# WindVane.net
KiCad netlist of a schematic drawn in EAGLE
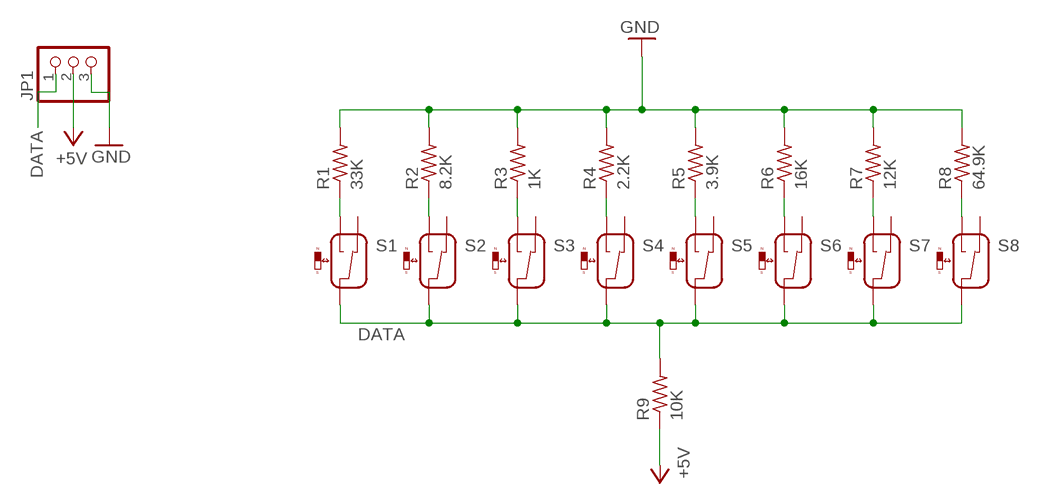
[diagram p0: schematic, sheet 1]

(export (version "E")
  (design (tool "Eeschema 10.0.6"))
  (components
    (comp (ref "JP1")
      (value "PINHD-1X3/90")
      (footprint "eagle-import:1X03_90")
      (libsource (lib "eagle-import") (part "PINHD-1X3/90"))
    )
    (comp (ref "R1")
      (value "33K")
      (footprint "eagle-import:0207_10")
      (libsource (lib "eagle-import") (part "R-US_0207/10"))
    )
    (comp (ref "R2")
      (value "8.2K")
      (footprint "eagle-import:0207_10")
      (libsource (lib "eagle-import") (part "R-US_0207/10"))
    )
    (comp (ref "R3")
      (value "1K")
      (footprint "eagle-import:0207_10")
      (libsource (lib "eagle-import") (part "R-US_0207/10"))
    )
    (comp (ref "R4")
      (value "2.2K")
      (footprint "eagle-import:0207_10")
      (libsource (lib "eagle-import") (part "R-US_0207/10"))
    )
    (comp (ref "R5")
      (value "3.9K")
      (footprint "eagle-import:0207_10")
      (libsource (lib "eagle-import") (part "R-US_0207/10"))
    )
    (comp (ref "R6")
      (value "16K")
      (footprint "eagle-import:0207_10")
      (libsource (lib "eagle-import") (part "R-US_0207/10"))
    )
    (comp (ref "R7")
      (value "12K")
      (footprint "eagle-import:0207_10")
      (libsource (lib "eagle-import") (part "R-US_0207/10"))
    )
    (comp (ref "R8")
      (value "64.9K")
      (footprint "eagle-import:0207_10")
      (libsource (lib "eagle-import") (part "R-US_0207/10"))
    )
    (comp (ref "R9")
      (value "10K")
      (footprint "eagle-import:0207_10")
      (libsource (lib "eagle-import") (part "R-US_0207/10"))
    )
    (comp (ref "S1")
      (value "REED-SWITCH-NO-NC")
      (footprint "eagle-import:MK6-8-C")
      (libsource (lib "eagle-import") (part "REED-SWITCH-NO-NC"))
    )
    (comp (ref "S2")
      (value "REED-SWITCH-NO-NC")
      (footprint "eagle-import:MK6-8-C")
      (libsource (lib "eagle-import") (part "REED-SWITCH-NO-NC"))
    )
    (comp (ref "S3")
      (value "REED-SWITCH-NO-NC")
      (footprint "eagle-import:MK6-8-C")
      (libsource (lib "eagle-import") (part "REED-SWITCH-NO-NC"))
    )
    (comp (ref "S4")
      (value "REED-SWITCH-NO-NC")
      (footprint "eagle-import:MK6-8-C")
      (libsource (lib "eagle-import") (part "REED-SWITCH-NO-NC"))
    )
    (comp (ref "S5")
      (value "REED-SWITCH-NO-NC")
      (footprint "eagle-import:MK6-8-C")
      (libsource (lib "eagle-import") (part "REED-SWITCH-NO-NC"))
    )
    (comp (ref "S6")
      (value "REED-SWITCH-NO-NC")
      (footprint "eagle-import:MK6-8-C")
      (libsource (lib "eagle-import") (part "REED-SWITCH-NO-NC"))
    )
    (comp (ref "S7")
      (value "REED-SWITCH-NO-NC")
      (footprint "eagle-import:MK6-8-C")
      (libsource (lib "eagle-import") (part "REED-SWITCH-NO-NC"))
    )
    (comp (ref "S8")
      (value "REED-SWITCH-NO-NC")
      (footprint "eagle-import:MK6-8-C")
      (libsource (lib "eagle-import") (part "REED-SWITCH-NO-NC"))
    )
  )
  (nets
    (net (code "1") (name "+5V") (class "Default")
      (node (ref "JP1") (pin "2") (pinfunction "2_2") (pintype "passive"))
      (node (ref "R9") (pin "1") (pinfunction "1_1") (pintype "passive"))
    )
    (net (code "2") (name "/DATA") (class "Default")
      (node (ref "JP1") (pin "1") (pinfunction "1_1") (pintype "passive"))
      (node (ref "R9") (pin "2") (pinfunction "2_2") (pintype "passive"))
      (node (ref "S1") (pin "COM") (pinfunction "COM_COM") (pintype "passive"))
      (node (ref "S2") (pin "COM") (pinfunction "COM_COM") (pintype "passive"))
      (node (ref "S3") (pin "COM") (pinfunction "COM_COM") (pintype "passive"))
      (node (ref "S4") (pin "COM") (pinfunction "COM_COM") (pintype "passive"))
      (node (ref "S5") (pin "COM") (pinfunction "COM_COM") (pintype "passive"))
      (node (ref "S6") (pin "COM") (pinfunction "COM_COM") (pintype "passive"))
      (node (ref "S7") (pin "COM") (pinfunction "COM_COM") (pintype "passive"))
      (node (ref "S8") (pin "COM") (pinfunction "COM_COM") (pintype "passive"))
    )
    (net (code "3") (name "GND") (class "Default")
      (node (ref "JP1") (pin "3") (pinfunction "3_3") (pintype "passive"))
      (node (ref "R1") (pin "2") (pinfunction "2_2") (pintype "passive"))
      (node (ref "R2") (pin "2") (pinfunction "2_2") (pintype "passive"))
      (node (ref "R3") (pin "2") (pinfunction "2_2") (pintype "passive"))
      (node (ref "R4") (pin "2") (pinfunction "2_2") (pintype "passive"))
      (node (ref "R5") (pin "2") (pinfunction "2_2") (pintype "passive"))
      (node (ref "R6") (pin "2") (pinfunction "2_2") (pintype "passive"))
      (node (ref "R7") (pin "2") (pinfunction "2_2") (pintype "passive"))
      (node (ref "R8") (pin "2") (pinfunction "2_2") (pintype "passive"))
    )
    (net (code "4") (name "Net-(R1-Pad1)") (class "Default")
      (node (ref "R1") (pin "1") (pinfunction "1_1") (pintype "passive"))
      (node (ref "S1") (pin "NO") (pinfunction "NO_NO") (pintype "passive"))
    )
    (net (code "5") (name "Net-(R2-Pad1)") (class "Default")
      (node (ref "R2") (pin "1") (pinfunction "1_1") (pintype "passive"))
      (node (ref "S2") (pin "NO") (pinfunction "NO_NO") (pintype "passive"))
    )
    (net (code "6") (name "Net-(R3-Pad1)") (class "Default")
      (node (ref "R3") (pin "1") (pinfunction "1_1") (pintype "passive"))
      (node (ref "S3") (pin "NO") (pinfunction "NO_NO") (pintype "passive"))
    )
    (net (code "7") (name "Net-(R4-Pad1)") (class "Default")
      (node (ref "R4") (pin "1") (pinfunction "1_1") (pintype "passive"))
      (node (ref "S4") (pin "NO") (pinfunction "NO_NO") (pintype "passive"))
    )
    (net (code "8") (name "Net-(R5-Pad1)") (class "Default")
      (node (ref "R5") (pin "1") (pinfunction "1_1") (pintype "passive"))
      (node (ref "S5") (pin "NO") (pinfunction "NO_NO") (pintype "passive"))
    )
    (net (code "9") (name "Net-(R6-Pad1)") (class "Default")
      (node (ref "R6") (pin "1") (pinfunction "1_1") (pintype "passive"))
      (node (ref "S6") (pin "NO") (pinfunction "NO_NO") (pintype "passive"))
    )
    (net (code "10") (name "Net-(R7-Pad1)") (class "Default")
      (node (ref "R7") (pin "1") (pinfunction "1_1") (pintype "passive"))
      (node (ref "S7") (pin "NO") (pinfunction "NO_NO") (pintype "passive"))
    )
    (net (code "11") (name "Net-(R8-Pad1)") (class "Default")
      (node (ref "R8") (pin "1") (pinfunction "1_1") (pintype "passive"))
      (node (ref "S8") (pin "NO") (pinfunction "NO_NO") (pintype "passive"))
    )
    (net (code "12") (name "unconnected-(S1-PadNC)") (class "Default")
      (node (ref "S1") (pin "NC") (pinfunction "NC_NC") (pintype "passive"))
    )
    (net (code "13") (name "unconnected-(S2-PadNC)") (class "Default")
      (node (ref "S2") (pin "NC") (pinfunction "NC_NC") (pintype "passive"))
    )
    (net (code "14") (name "unconnected-(S3-PadNC)") (class "Default")
      (node (ref "S3") (pin "NC") (pinfunction "NC_NC") (pintype "passive"))
    )
    (net (code "15") (name "unconnected-(S4-PadNC)") (class "Default")
      (node (ref "S4") (pin "NC") (pinfunction "NC_NC") (pintype "passive"))
    )
    (net (code "16") (name "unconnected-(S5-PadNC)") (class "Default")
      (node (ref "S5") (pin "NC") (pinfunction "NC_NC") (pintype "passive"))
    )
    (net (code "17") (name "unconnected-(S6-PadNC)") (class "Default")
      (node (ref "S6") (pin "NC") (pinfunction "NC_NC") (pintype "passive"))
    )
    (net (code "18") (name "unconnected-(S7-PadNC)") (class "Default")
      (node (ref "S7") (pin "NC") (pinfunction "NC_NC") (pintype "passive"))
    )
    (net (code "19") (name "unconnected-(S8-PadNC)") (class "Default")
      (node (ref "S8") (pin "NC") (pinfunction "NC_NC") (pintype "passive"))
    )
  )
)
